# HedleySensorRevC.net
KiCad netlist of a schematic drawn in EAGLE
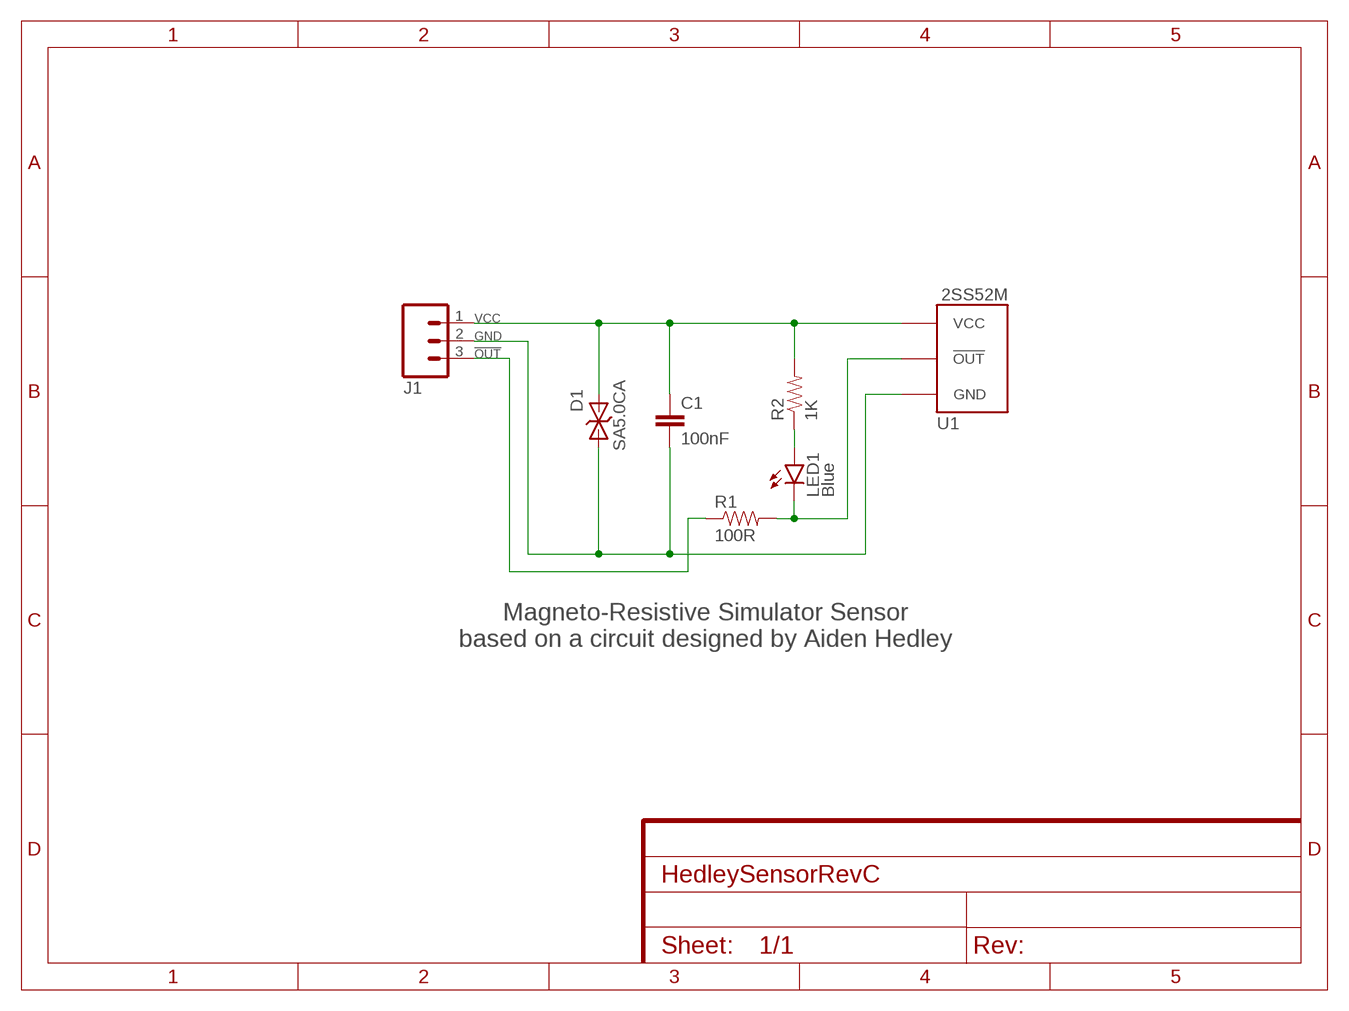
[diagram p0: schematic, sheet 1]

(export (version "E")
  (design (tool "Eeschema 10.0.6"))
  (components
    (comp (ref "C1")
      (value "100nF")
      (footprint "eagle-import:CAP-PTH-SMALL")
      (libsource (lib "eagle-import") (part "CAPPTH"))
    )
    (comp (ref "D1")
      (value "SA5.0CA")
      (footprint "eagle-import:DO41_TVS")
      (libsource (lib "eagle-import") (part "SA5.0CA"))
    )
    (comp (ref "J1")
      (value "M03PTH")
      (footprint "eagle-import:1X03")
      (libsource (lib "eagle-import") (part "M03PTH"))
    )
    (comp (ref "LED1")
      (value "Blue")
      (footprint "eagle-import:LED3MM")
      (libsource (lib "eagle-import") (part "LED3MM"))
    )
    (comp (ref "R1")
      (value "100R")
      (footprint "eagle-import:AXIAL-0.4")
      (libsource (lib "eagle-import") (part "RESISTORPTH-1/4W"))
    )
    (comp (ref "R2")
      (value "1K")
      (footprint "eagle-import:AXIAL-0.4")
      (libsource (lib "eagle-import") (part "RESISTORPTH-1/4W"))
    )
    (comp (ref "U1")
      (value "2SS52MFLAT")
      (footprint "eagle-import:2SS52M_FLAT")
      (libsource (lib "eagle-import") (part "2SS52MFLAT"))
    )
  )
  (nets
    (net (code "1") (name "/GND") (class "Default")
      (node (ref "C1") (pin "2") (pinfunction "2_2") (pintype "passive"))
      (node (ref "D1") (pin "A") (pinfunction "A_A") (pintype "passive"))
      (node (ref "J1") (pin "2") (pinfunction "2_2") (pintype "passive"))
      (node (ref "U1") (pin "P$1") (pinfunction "GND_P$1") (pintype "bidirectional"))
    )
    (net (code "2") (name "/VCC") (class "Default")
      (node (ref "C1") (pin "1") (pinfunction "1_1") (pintype "passive"))
      (node (ref "D1") (pin "C") (pinfunction "C_C") (pintype "passive"))
      (node (ref "J1") (pin "1") (pinfunction "1_1") (pintype "passive"))
      (node (ref "R2") (pin "P$2") (pinfunction "2_P$2") (pintype "passive"))
      (node (ref "U1") (pin "P$3") (pinfunction "VCC_P$3") (pintype "bidirectional"))
    )
    (net (code "3") (name "/~{OUT}") (class "Default")
      (node (ref "J1") (pin "3") (pinfunction "3_3") (pintype "passive"))
      (node (ref "R1") (pin "P$1") (pinfunction "1_P$1") (pintype "passive"))
    )
    (net (code "4") (name "Net-(LED1-C)") (class "Default")
      (node (ref "LED1") (pin "K") (pinfunction "C_K") (pintype "passive"))
      (node (ref "R1") (pin "P$2") (pinfunction "2_P$2") (pintype "passive"))
      (node (ref "U1") (pin "P$2") (pinfunction "~{OUT}_P$2") (pintype "bidirectional"))
    )
    (net (code "5") (name "Net-(R2-1)") (class "Default")
      (node (ref "LED1") (pin "A") (pinfunction "A_A") (pintype "passive"))
      (node (ref "R2") (pin "P$1") (pinfunction "1_P$1") (pintype "passive"))
    )
  )
)
